# RTC.net
KiCad netlist of a schematic drawn in Altium Designer
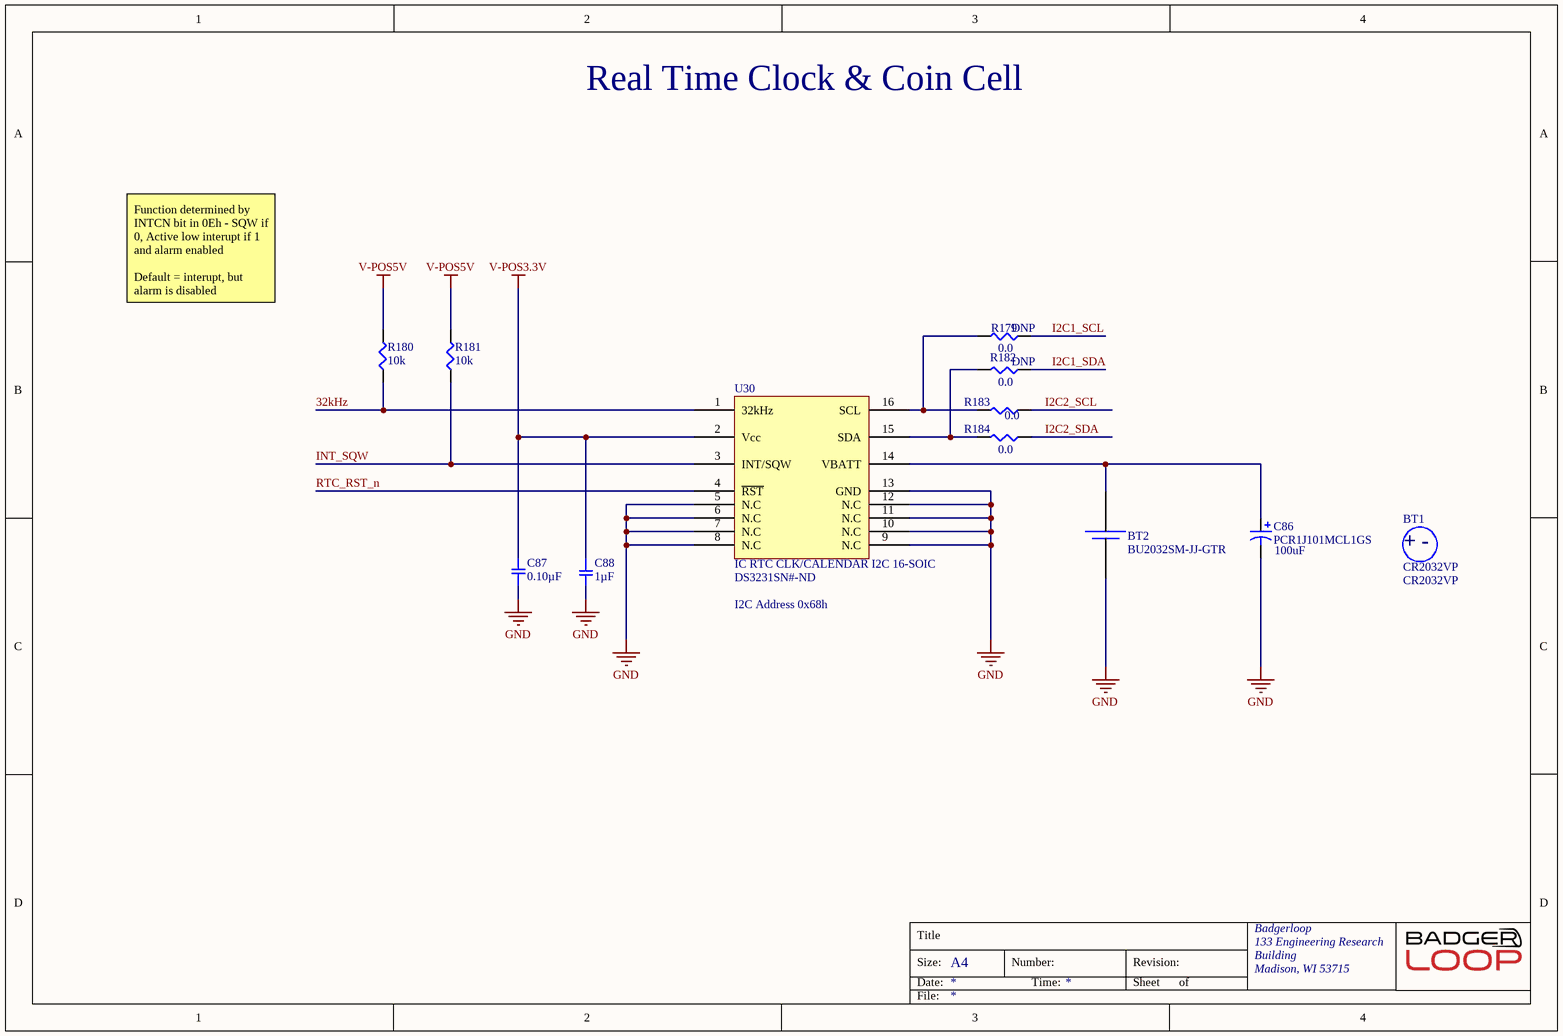
[diagram p0: RTC.SchDoc]

(export (version "E")
  (design (tool "Eeschema 10.0.6"))
  (components
    (comp (ref "BT1")
      (value "CR2032VP")
      (description "BATTERY LITHIUM 3V COIN 20MM")
      (fields (field (name "MANUFACTURER") "Energizer") (field (name "MANUFACTURER PART NUMBER") "CR2032VP"))
      (libsource (lib "misc") (part "CR2032VP"))
    )
    (comp (ref "BT2")
      (value "BU2032SM-JJ-GTR")
      (footprint "BATTERY HOLDER COIN 20MM")
      (description "HOLDER COIN CELL 2032 SMD")
      (fields (field (name "MANUFACTURER") "Memory Protection Devices"))
      (libsource (lib "misc") (part "BU2032SM-JJ-GTR"))
    )
    (comp (ref "C86")
      (value "PCR1J101MCL1GS")
      (footprint "CAPAE110103X126M")
      (description "CAP ALUM POLY 100UF 20% 63V SMD")
      (fields
        (field (name "MANUFACTURER") "Nichicon")
        (field (name "CAPACITANCE") "100uF")
        (field (name "TOLERANCE") "20%")
      )
      (libsource (lib "capacitors") (part "PCR1J101MCL1GS"))
    )
    (comp (ref "C87")
      (value "0.10µF")
      (footprint "SMD-0805C")
      (description "CAP CER 0.1UF 16V X7R 0805")
      (fields
        (field (name "DIGI-KEY PART NUMBER") "490-12557-1-ND")
        (field (name "PART NUMBER") "GRM219R71C104JA01D")
      )
      (libsource (lib "capacitors") (part "GRM219R71C104JA01D"))
    )
    (comp (ref "C88")
      (value "1µF")
      (footprint "SMD-0805C")
      (description "CAP CER 1UF 50V X7R 0805")
      (fields
        (field (name "DIGI-KEY PART NUMBER") "490-4736-1-ND")
        (field (name "PART NUMBER") "GRM21BR71H105KA12L")
      )
      (libsource (lib "capacitors") (part "GRM21BR71H105KA12L"))
    )
    (comp (ref "R179")
      (value "0.0")
      (footprint "SMD-0805-RES")
      (description "RES SMD 0.0 OHM JUMPER 1/8W 0805")
      (fields
        (field (name "PART NUMBER") "ERJ-6GEY0R00V")
        (field (name "DIGI-KEY PART NUMBER") "P0.0ACT-ND")
        (field (name "DNP") "DNP")
      )
      (libsource (lib "resistors") (part "ERJ-6GEY0R00V"))
    )
    (comp (ref "R180")
      (value "10k")
      (footprint "SMD-0805-RES")
      (description "RES SMD 10K OHM 5% 1/2W 0805")
      (fields (field (name "PART NUMBER") "ERJ-P06J103V") (field (name "DIGI-KEY PART NUMBER") "P10KADCT-ND"))
      (libsource (lib "resistors") (part "ERJ-P06J103V"))
    )
    (comp (ref "R181")
      (value "10k")
      (footprint "SMD-0805-RES")
      (description "RES SMD 10K OHM 5% 1/2W 0805")
      (fields (field (name "PART NUMBER") "ERJ-P06J103V") (field (name "DIGI-KEY PART NUMBER") "P10KADCT-ND"))
      (libsource (lib "resistors") (part "ERJ-P06J103V"))
    )
    (comp (ref "R182")
      (value "0.0")
      (footprint "SMD-0805-RES")
      (description "RES SMD 0.0 OHM JUMPER 1/8W 0805")
      (fields
        (field (name "PART NUMBER") "ERJ-6GEY0R00V")
        (field (name "DIGI-KEY PART NUMBER") "P0.0ACT-ND")
        (field (name "DNP") "DNP")
      )
      (libsource (lib "resistors") (part "ERJ-6GEY0R00V"))
    )
    (comp (ref "R183")
      (value "0.0")
      (footprint "SMD-0805-RES")
      (description "RES SMD 0.0 OHM JUMPER 1/8W 0805")
      (fields (field (name "PART NUMBER") "ERJ-6GEY0R00V") (field (name "DIGI-KEY PART NUMBER") "P0.0ACT-ND"))
      (libsource (lib "resistors") (part "ERJ-6GEY0R00V"))
    )
    (comp (ref "R184")
      (value "0.0")
      (footprint "SMD-0805-RES")
      (description "RES SMD 0.0 OHM JUMPER 1/8W 0805")
      (fields (field (name "PART NUMBER") "ERJ-6GEY0R00V") (field (name "DIGI-KEY PART NUMBER") "P0.0ACT-ND"))
      (libsource (lib "resistors") (part "ERJ-6GEY0R00V"))
    )
    (comp (ref "U30")
      (value "IC RTC CLK/CALENDAR I2C 16-SOIC")
      (footprint "SOP127P1030X265-16N")
      (fields
        (field (name "MANUFACTURER") "Maxim")
        (field (name "MANUFACTURER PART NUMBER") "DS3231SN#")
        (field (name "SUPPLIER PART NUMBER 1") "DS3231SN#-ND")
      )
      (libsource (lib "ic") (part "DS3231"))
    )
  )
  (nets
    (net (code "1") (name "/32kHz") (class "Default")
      (node (ref "R180") (pin "1") (pinfunction "1_1") (pintype "passive"))
      (node (ref "U30") (pin "1") (pinfunction "32kHz_1") (pintype "passive"))
    )
    (net (code "2") (name "/I2C1_SCL") (class "Default")
      (node (ref "R179") (pin "1") (pinfunction "1_1") (pintype "passive"))
    )
    (net (code "3") (name "/I2C1_SDA") (class "Default")
      (node (ref "R182") (pin "1") (pinfunction "1_1") (pintype "passive"))
    )
    (net (code "4") (name "/I2C2_SCL") (class "Default")
      (node (ref "R183") (pin "1") (pinfunction "1_1") (pintype "passive"))
    )
    (net (code "5") (name "/I2C2_SDA") (class "Default")
      (node (ref "R184") (pin "1") (pinfunction "1_1") (pintype "passive"))
    )
    (net (code "6") (name "/INT_SQW") (class "Default")
      (node (ref "R181") (pin "1") (pinfunction "1_1") (pintype "passive"))
      (node (ref "U30") (pin "3") (pinfunction "INT/SQW_3") (pintype "passive"))
    )
    (net (code "7") (name "/RTC_RST_n") (class "Default")
      (node (ref "U30") (pin "4") (pinfunction "RST_4") (pintype "passive"))
    )
    (net (code "8") (name "GND") (class "Default")
      (node (ref "BT2") (pin "1") (pinfunction "+_1") (pintype "passive"))
      (node (ref "C86") (pin "2") (pinfunction "2_2") (pintype "passive"))
      (node (ref "C87") (pin "1") (pinfunction "1_1") (pintype "passive"))
      (node (ref "C88") (pin "2") (pinfunction "2_2") (pintype "passive"))
      (node (ref "U30") (pin "10") (pinfunction "N.C_10") (pintype "passive"))
      (node (ref "U30") (pin "11") (pinfunction "N.C_11") (pintype "passive"))
      (node (ref "U30") (pin "12") (pinfunction "N.C_12") (pintype "passive"))
      (node (ref "U30") (pin "13") (pinfunction "GND_13") (pintype "passive"))
      (node (ref "U30") (pin "5") (pinfunction "N.C_5") (pintype "passive"))
      (node (ref "U30") (pin "6") (pinfunction "N.C_6") (pintype "passive"))
      (node (ref "U30") (pin "7") (pinfunction "N.C_7") (pintype "passive"))
      (node (ref "U30") (pin "8") (pinfunction "N.C_8") (pintype "passive"))
      (node (ref "U30") (pin "9") (pinfunction "N.C_9") (pintype "passive"))
    )
    (net (code "9") (name "Net-(BT2--)") (class "Default")
      (node (ref "BT2") (pin "2") (pinfunction "-_2") (pintype "passive"))
      (node (ref "C86") (pin "1") (pinfunction "1_1") (pintype "passive"))
      (node (ref "U30") (pin "14") (pinfunction "VBATT_14") (pintype "passive"))
    )
    (net (code "10") (name "Net-(U30-SCL)") (class "Default")
      (node (ref "R179") (pin "2") (pinfunction "2_2") (pintype "passive"))
      (node (ref "R183") (pin "2") (pinfunction "2_2") (pintype "passive"))
      (node (ref "U30") (pin "16") (pinfunction "SCL_16") (pintype "passive"))
    )
    (net (code "11") (name "Net-(U30-SDA)") (class "Default")
      (node (ref "R182") (pin "2") (pinfunction "2_2") (pintype "passive"))
      (node (ref "R184") (pin "2") (pinfunction "2_2") (pintype "passive"))
      (node (ref "U30") (pin "15") (pinfunction "SDA_15") (pintype "passive"))
    )
    (net (code "12") (name "V-POS3.3V") (class "Default")
      (node (ref "C87") (pin "2") (pinfunction "2_2") (pintype "passive"))
      (node (ref "C88") (pin "1") (pinfunction "1_1") (pintype "passive"))
      (node (ref "U30") (pin "2") (pinfunction "Vcc_2") (pintype "passive"))
    )
    (net (code "13") (name "V-POS5V") (class "Default")
      (node (ref "R180") (pin "2") (pinfunction "2_2") (pintype "passive"))
      (node (ref "R181") (pin "2") (pinfunction "2_2") (pintype "passive"))
    )
  )
)
